# 04_Sensor.net
KiCad netlist of a schematic drawn in Altium Designer
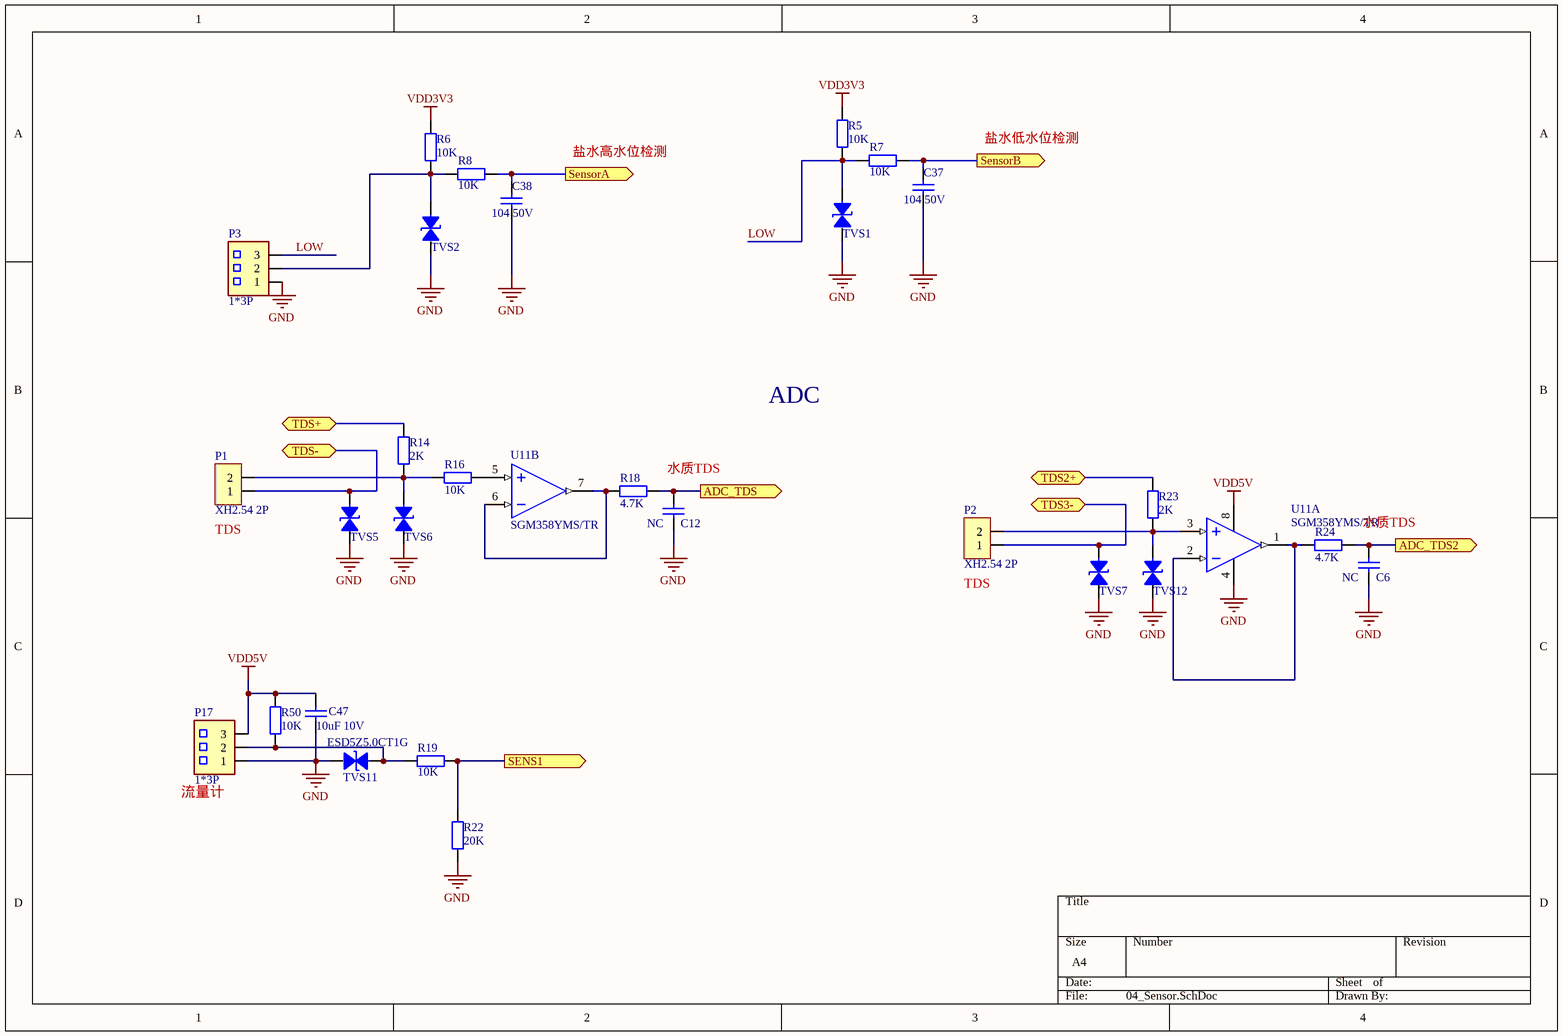
[diagram p0: 04_Sensor.SchDoc]

(export (version "E")
  (design (tool "Eeschema 10.0.6"))
  (components
    (comp (ref "C6")
      (value "NC")
      (footprint "0603C")
      (description "贴片电容 10%")
      (libsource (lib "XiaoyI") (part "CAP4"))
    )
    (comp (ref "C12")
      (value "NC")
      (footprint "SMD-0603C")
      (description "贴片电容 10%")
      (libsource (lib "XiaoyI") (part "CAP4"))
    )
    (comp (ref "C37")
      (value "104 50V")
      (footprint "SMD-0603C")
      (description "贴片电容 20%")
      (libsource (lib "XiaoyI") (part "CAP4"))
    )
    (comp (ref "C38")
      (value "104 50V")
      (footprint "SMD-0603C")
      (description "贴片电容 20%")
      (libsource (lib "XiaoyI") (part "CAP4"))
    )
    (comp (ref "C47")
      (value "10uF 10V")
      (footprint "SMD-0603C")
      (description "贴片电容 10%")
      (libsource (lib "Miscellaneous Devices LC") (part "0805 22uF (226) 20% 25V"))
    )
    (comp (ref "P1")
      (value "XH2.54 2P")
      (footprint "SIP-2A")
      (description "XH2.54 2P 直插")
      (libsource (lib "XiaoyI") (part "SIP-2"))
    )
    (comp (ref "P2")
      (value "XH2.54 2P")
      (footprint "SIP-2A")
      (description "XH2.54 2P 直插")
      (libsource (lib "XiaoyI") (part "SIP-2"))
    )
    (comp (ref "P3") (value "1*3P") (footprint "3X2MMZ") (libsource (lib "PARK-N5 V1.0") (part "HDR1*3")))
    (comp (ref "P17")
      (value "1*3P")
      (footprint "3X2.54MMZ2")
      (libsource (lib "PARK-N5 V1.0") (part "HDR1*3"))
    )
    (comp (ref "R5")
      (value "10K")
      (footprint "SMD-0603")
      (description "贴片电阻 1%")
      (libsource (lib "") (part "RES0_1"))
    )
    (comp (ref "R6")
      (value "10K")
      (footprint "SMD-0603")
      (description "贴片电阻 1%")
      (libsource (lib "") (part "RES0_1"))
    )
    (comp (ref "R7")
      (value "10K")
      (footprint "SMD-0603")
      (description "贴片电阻 1%")
      (libsource (lib "") (part "RES0_2"))
    )
    (comp (ref "R8")
      (value "10K")
      (footprint "SMD-0603")
      (description "贴片电阻 1%")
      (libsource (lib "") (part "RES0_2"))
    )
    (comp (ref "R14")
      (value "2K")
      (footprint "SMD-0603")
      (description "贴片电阻 1%")
      (libsource (lib "") (part "RES0_1"))
    )
    (comp (ref "R16")
      (value "10K")
      (footprint "SMD-0603")
      (description "贴片电阻 1%")
      (libsource (lib "") (part "RES0_2"))
    )
    (comp (ref "R18")
      (value "4.7K")
      (footprint "SMD-0603")
      (description "贴片电阻 5%")
      (libsource (lib "ABB") (part "RES0"))
    )
    (comp (ref "R19")
      (value "10K")
      (footprint "SMD-0603")
      (description "贴片电阻 5%")
      (libsource (lib "") (part "0603 10KΩ (1002) 1%_2"))
    )
    (comp (ref "R22")
      (value "20K")
      (footprint "SMD-0603")
      (description "贴片电阻 5%")
      (libsource (lib "Miscellaneous Devices LC") (part "0603 10KΩ (1002) 1%"))
    )
    (comp (ref "R23")
      (value "2K")
      (footprint "0603R")
      (description "贴片电阻 1%")
      (libsource (lib "") (part "RES0_1"))
    )
    (comp (ref "R24")
      (value "4.7K")
      (footprint "0603R")
      (description "贴片电阻 5%")
      (libsource (lib "ABB") (part "RES0"))
    )
    (comp (ref "R50")
      (value "10K")
      (footprint "SMD-0603")
      (description "贴片电阻 5%")
      (libsource (lib "") (part "0603 10KΩ (1002) 1%_1"))
    )
    (comp (ref "TVS1")
      (value "ESD5Z5.0CT1G")
      (footprint "SOD-523")
      (description "TVS")
      (libsource (lib "XiaoyI") (part "TVS-1"))
    )
    (comp (ref "TVS2")
      (value "ESD5Z5.0CT1G")
      (footprint "SOD-523")
      (description "TVS")
      (libsource (lib "XiaoyI") (part "TVS-1"))
    )
    (comp (ref "TVS5")
      (value "ESD5Z5.0CT1G")
      (footprint "SOD-523")
      (description "TVS")
      (libsource (lib "XiaoyI") (part "TVS-1"))
    )
    (comp (ref "TVS6")
      (value "ESD5Z5.0CT1G")
      (footprint "SOD-523")
      (description "TVS")
      (libsource (lib "XiaoyI") (part "TVS-1"))
    )
    (comp (ref "TVS7")
      (value "ESD5Z5.0CT1G")
      (footprint "SOD-523")
      (description "TVS")
      (libsource (lib "XiaoyI") (part "TVS-1"))
    )
    (comp (ref "TVS11")
      (value "ESD5Z5.0CT1G")
      (footprint "SOD-523")
      (description "TVS 5.0V")
      (libsource (lib "XiaoyI") (part "TVS-1"))
    )
    (comp (ref "TVS12")
      (value "ESD5Z5.0CT1G")
      (footprint "SOD-523")
      (description "TVS")
      (libsource (lib "XiaoyI") (part "TVS-1"))
    )
    (comp (ref "U11")
      (value "SGM358YMS/TR")
      (footprint "MSOP-8")
      (description "运放")
      (libsource (lib "XiaoyI") (part "LM358"))
    )
  )
  (nets
    (net (code "1") (name "/ADC_TDS") (class "Default")
      (node (ref "C12") (pin "2") (pinfunction "2_2") (pintype "passive"))
      (node (ref "R18") (pin "1") (pinfunction "1_1") (pintype "passive"))
    )
    (net (code "2") (name "/ADC_TDS2") (class "Default")
      (node (ref "C6") (pin "2") (pinfunction "2_2") (pintype "passive"))
      (node (ref "R24") (pin "1") (pinfunction "1_1") (pintype "passive"))
    )
    (net (code "3") (name "/LOW") (class "Default")
      (node (ref "P3") (pin "3") (pinfunction "3_3") (pintype "passive"))
      (node (ref "R5") (pin "2") (pinfunction "2_2") (pintype "passive"))
      (node (ref "R7") (pin "1") (pinfunction "1_1") (pintype "passive"))
      (node (ref "TVS1") (pin "2") (pinfunction "B_2") (pintype "passive"))
    )
    (net (code "4") (name "/SENS1") (class "Default")
      (node (ref "R19") (pin "2") (pinfunction "2_2") (pintype "passive"))
      (node (ref "R22") (pin "2") (pinfunction "2_2") (pintype "passive"))
    )
    (net (code "5") (name "/SensorA") (class "Default")
      (node (ref "C38") (pin "2") (pinfunction "2_2") (pintype "passive"))
      (node (ref "R8") (pin "2") (pinfunction "2_2") (pintype "passive"))
    )
    (net (code "6") (name "/SensorB") (class "Default")
      (node (ref "C37") (pin "2") (pinfunction "2_2") (pintype "passive"))
      (node (ref "R7") (pin "2") (pinfunction "2_2") (pintype "passive"))
    )
    (net (code "7") (name "/TDS+") (class "Default")
      (node (ref "R14") (pin "1") (pinfunction "1_1") (pintype "passive"))
    )
    (net (code "8") (name "/TDS-") (class "Default")
      (node (ref "P1") (pin "1") (pinfunction "1_1") (pintype "passive"))
      (node (ref "TVS5") (pin "2") (pinfunction "B_2") (pintype "passive"))
    )
    (net (code "9") (name "/TDS2+") (class "Default")
      (node (ref "R23") (pin "1") (pinfunction "1_1") (pintype "passive"))
    )
    (net (code "10") (name "/TDS3-") (class "Default")
      (node (ref "P2") (pin "1") (pinfunction "1_1") (pintype "passive"))
      (node (ref "TVS7") (pin "2") (pinfunction "B_2") (pintype "passive"))
    )
    (net (code "11") (name "GND") (class "Default")
      (node (ref "C12") (pin "1") (pinfunction "1_1") (pintype "passive"))
      (node (ref "C37") (pin "1") (pinfunction "1_1") (pintype "passive"))
      (node (ref "C38") (pin "1") (pinfunction "1_1") (pintype "passive"))
      (node (ref "C47") (pin "1") (pinfunction "1_1") (pintype "passive"))
      (node (ref "C6") (pin "1") (pinfunction "1_1") (pintype "passive"))
      (node (ref "P17") (pin "1") (pinfunction "1_1") (pintype "passive"))
      (node (ref "P3") (pin "1") (pinfunction "1_1") (pintype "passive"))
      (node (ref "R22") (pin "1") (pinfunction "1_1") (pintype "passive"))
      (node (ref "TVS1") (pin "1") (pinfunction "A_1") (pintype "passive"))
      (node (ref "TVS11") (pin "1") (pinfunction "A_1") (pintype "passive"))
      (node (ref "TVS12") (pin "1") (pinfunction "A_1") (pintype "passive"))
      (node (ref "TVS2") (pin "1") (pinfunction "A_1") (pintype "passive"))
      (node (ref "TVS5") (pin "1") (pinfunction "A_1") (pintype "passive"))
      (node (ref "TVS6") (pin "1") (pinfunction "A_1") (pintype "passive"))
      (node (ref "TVS7") (pin "1") (pinfunction "A_1") (pintype "passive"))
      (node (ref "U11") (pin "4") (pinfunction "V-_4") (pintype "power_in"))
    )
    (net (code "12") (name "Net-(TVS2-B)") (class "Default")
      (node (ref "P3") (pin "2") (pinfunction "2_2") (pintype "passive"))
      (node (ref "R6") (pin "2") (pinfunction "2_2") (pintype "passive"))
      (node (ref "R8") (pin "1") (pinfunction "1_1") (pintype "passive"))
      (node (ref "TVS2") (pin "2") (pinfunction "B_2") (pintype "passive"))
    )
    (net (code "13") (name "Net-(TVS6-B)") (class "Default")
      (node (ref "P1") (pin "2") (pinfunction "2_2") (pintype "passive"))
      (node (ref "R14") (pin "2") (pinfunction "2_2") (pintype "passive"))
      (node (ref "R16") (pin "1") (pinfunction "1_1") (pintype "passive"))
      (node (ref "TVS6") (pin "2") (pinfunction "B_2") (pintype "passive"))
    )
    (net (code "14") (name "Net-(TVS11-B)") (class "Default")
      (node (ref "P17") (pin "2") (pinfunction "2_2") (pintype "passive"))
      (node (ref "R19") (pin "1") (pinfunction "1_1") (pintype "passive"))
      (node (ref "R50") (pin "2") (pinfunction "2_2") (pintype "passive"))
      (node (ref "TVS11") (pin "2") (pinfunction "B_2") (pintype "passive"))
    )
    (net (code "15") (name "Net-(TVS12-B)") (class "Default")
      (node (ref "P2") (pin "2") (pinfunction "2_2") (pintype "passive"))
      (node (ref "R23") (pin "2") (pinfunction "2_2") (pintype "passive"))
      (node (ref "TVS12") (pin "2") (pinfunction "B_2") (pintype "passive"))
      (node (ref "U11") (pin "3") (pinfunction "IN1+_3") (pintype "input"))
    )
    (net (code "16") (name "Net-(U11A-IN1-)") (class "Default")
      (node (ref "R24") (pin "2") (pinfunction "2_2") (pintype "passive"))
      (node (ref "U11") (pin "1") (pinfunction "OUT1_1") (pintype "output"))
      (node (ref "U11") (pin "2") (pinfunction "IN1-_2") (pintype "input"))
    )
    (net (code "17") (name "Net-(U11B-IN2+)") (class "Default")
      (node (ref "R16") (pin "2") (pinfunction "2_2") (pintype "passive"))
      (node (ref "U11") (pin "5") (pinfunction "IN2+_5") (pintype "input"))
    )
    (net (code "18") (name "Net-(U11B-IN2-)") (class "Default")
      (node (ref "R18") (pin "2") (pinfunction "2_2") (pintype "passive"))
      (node (ref "U11") (pin "6") (pinfunction "IN2-_6") (pintype "input"))
      (node (ref "U11") (pin "7") (pinfunction "OUT2_7") (pintype "output"))
    )
    (net (code "19") (name "VDD3V3") (class "Default")
      (node (ref "R5") (pin "1") (pinfunction "1_1") (pintype "passive"))
      (node (ref "R6") (pin "1") (pinfunction "1_1") (pintype "passive"))
    )
    (net (code "20") (name "VDD5V") (class "Default")
      (node (ref "C47") (pin "2") (pinfunction "2_2") (pintype "passive"))
      (node (ref "P17") (pin "3") (pinfunction "3_3") (pintype "passive"))
      (node (ref "R50") (pin "1") (pinfunction "1_1") (pintype "passive"))
      (node (ref "U11") (pin "8") (pinfunction "V+_8") (pintype "power_in"))
    )
  )
)
